# R302K.net
KiCad netlist of a schematic drawn in EAGLE
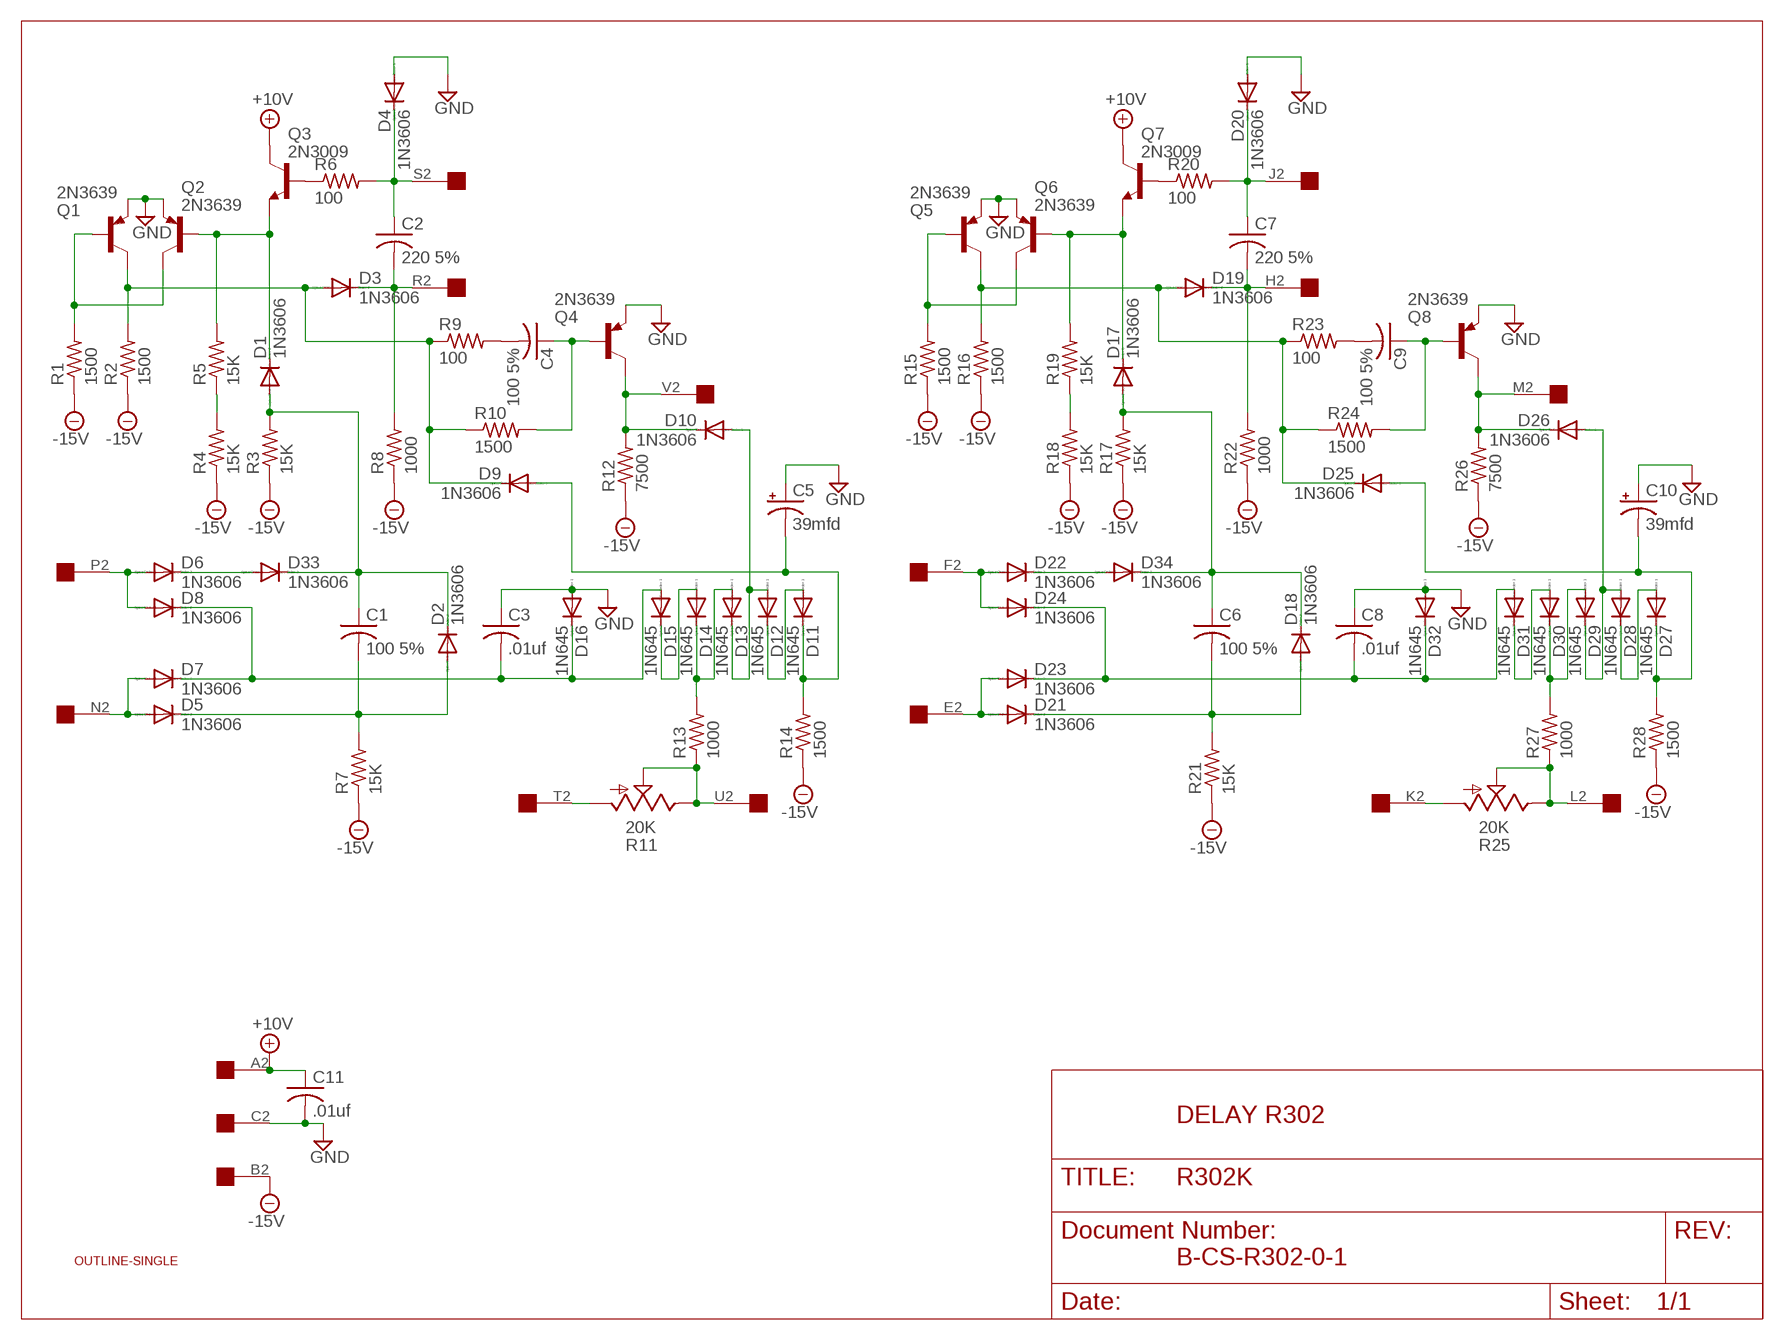
[diagram p0: schematic, sheet 1]

(export (version "E")
  (design (tool "Eeschema 10.0.6"))
  (components
    (comp (ref "C1")
      (value "100 5%")
      (footprint "eagle-import:C050-025X075")
      (libsource (lib "eagle-import") (part "C-US050-025X075"))
    )
    (comp (ref "C2")
      (value "220 5%")
      (footprint "eagle-import:C050-025X075")
      (libsource (lib "eagle-import") (part "C-US050-025X075"))
    )
    (comp (ref "C3")
      (value ".01uf")
      (footprint "eagle-import:C050-025X075")
      (libsource (lib "eagle-import") (part "C-US050-025X075"))
    )
    (comp (ref "C4")
      (value "100 5%")
      (footprint "eagle-import:C050-025X075")
      (libsource (lib "eagle-import") (part "C-US050-025X075"))
    )
    (comp (ref "C5")
      (value "39mfd")
      (footprint "eagle-import:E15-5")
      (libsource (lib "eagle-import") (part "CPOL-USE15-5AXIAL"))
    )
    (comp (ref "C6")
      (value "100 5%")
      (footprint "eagle-import:C050-025X075")
      (libsource (lib "eagle-import") (part "C-US050-025X075"))
    )
    (comp (ref "C7")
      (value "220 5%")
      (footprint "eagle-import:C050-025X075")
      (libsource (lib "eagle-import") (part "C-US050-025X075"))
    )
    (comp (ref "C8")
      (value ".01uf")
      (footprint "eagle-import:C050-025X075")
      (libsource (lib "eagle-import") (part "C-US050-025X075"))
    )
    (comp (ref "C9")
      (value "100 5%")
      (footprint "eagle-import:C050-025X075")
      (libsource (lib "eagle-import") (part "C-US050-025X075"))
    )
    (comp (ref "C10")
      (value "39mfd")
      (footprint "eagle-import:E15-5")
      (libsource (lib "eagle-import") (part "CPOL-USE15-5AXIAL"))
    )
    (comp (ref "C11")
      (value ".01uf")
      (footprint "eagle-import:C050-025X075")
      (libsource (lib "eagle-import") (part "C-US050-025X075"))
    )
    (comp (ref "D1")
      (value "1N3606")
      (footprint "eagle-import:DO35-10")
      (libsource (lib "eagle-import") (part "1N4148DO35-10"))
    )
    (comp (ref "D2")
      (value "1N3606")
      (footprint "eagle-import:DO35-10")
      (libsource (lib "eagle-import") (part "1N4148DO35-10"))
    )
    (comp (ref "D3")
      (value "1N3606")
      (footprint "eagle-import:DO35-10")
      (libsource (lib "eagle-import") (part "1N4148DO35-10"))
    )
    (comp (ref "D4")
      (value "1N3606")
      (footprint "eagle-import:DO35-10")
      (libsource (lib "eagle-import") (part "1N4148DO35-10"))
    )
    (comp (ref "D5")
      (value "1N3606")
      (footprint "eagle-import:DO35-10")
      (libsource (lib "eagle-import") (part "1N4148DO35-10"))
    )
    (comp (ref "D6")
      (value "1N3606")
      (footprint "eagle-import:DO35-10")
      (libsource (lib "eagle-import") (part "1N4148DO35-10"))
    )
    (comp (ref "D7")
      (value "1N3606")
      (footprint "eagle-import:DO35-10")
      (libsource (lib "eagle-import") (part "1N4148DO35-10"))
    )
    (comp (ref "D8")
      (value "1N3606")
      (footprint "eagle-import:DO35-10")
      (libsource (lib "eagle-import") (part "1N4148DO35-10"))
    )
    (comp (ref "D9")
      (value "1N3606")
      (footprint "eagle-import:DO35-10")
      (libsource (lib "eagle-import") (part "1N4148DO35-10"))
    )
    (comp (ref "D10")
      (value "1N3606")
      (footprint "eagle-import:DO35-10")
      (libsource (lib "eagle-import") (part "1N4148DO35-10"))
    )
    (comp (ref "D11")
      (value "1N645")
      (footprint "eagle-import:DO35-10")
      (libsource (lib "eagle-import") (part "1N4148DO35-10"))
    )
    (comp (ref "D12")
      (value "1N645")
      (footprint "eagle-import:DO35-10")
      (libsource (lib "eagle-import") (part "1N4148DO35-10"))
    )
    (comp (ref "D13")
      (value "1N645")
      (footprint "eagle-import:DO35-10")
      (libsource (lib "eagle-import") (part "1N4148DO35-10"))
    )
    (comp (ref "D14")
      (value "1N645")
      (footprint "eagle-import:DO35-10")
      (libsource (lib "eagle-import") (part "1N4148DO35-10"))
    )
    (comp (ref "D15")
      (value "1N645")
      (footprint "eagle-import:DO35-10")
      (libsource (lib "eagle-import") (part "1N4148DO35-10"))
    )
    (comp (ref "D16")
      (value "1N645")
      (footprint "eagle-import:DO35-10")
      (libsource (lib "eagle-import") (part "1N4148DO35-10"))
    )
    (comp (ref "D17")
      (value "1N3606")
      (footprint "eagle-import:DO35-10")
      (libsource (lib "eagle-import") (part "1N4148DO35-10"))
    )
    (comp (ref "D18")
      (value "1N3606")
      (footprint "eagle-import:DO35-10")
      (libsource (lib "eagle-import") (part "1N4148DO35-10"))
    )
    (comp (ref "D19")
      (value "1N3606")
      (footprint "eagle-import:DO35-10")
      (libsource (lib "eagle-import") (part "1N4148DO35-10"))
    )
    (comp (ref "D20")
      (value "1N3606")
      (footprint "eagle-import:DO35-10")
      (libsource (lib "eagle-import") (part "1N4148DO35-10"))
    )
    (comp (ref "D21")
      (value "1N3606")
      (footprint "eagle-import:DO35-10")
      (libsource (lib "eagle-import") (part "1N4148DO35-10"))
    )
    (comp (ref "D22")
      (value "1N3606")
      (footprint "eagle-import:DO35-10")
      (libsource (lib "eagle-import") (part "1N4148DO35-10"))
    )
    (comp (ref "D23")
      (value "1N3606")
      (footprint "eagle-import:DO35-10")
      (libsource (lib "eagle-import") (part "1N4148DO35-10"))
    )
    (comp (ref "D24")
      (value "1N3606")
      (footprint "eagle-import:DO35-10")
      (libsource (lib "eagle-import") (part "1N4148DO35-10"))
    )
    (comp (ref "D25")
      (value "1N3606")
      (footprint "eagle-import:DO35-10")
      (libsource (lib "eagle-import") (part "1N4148DO35-10"))
    )
    (comp (ref "D26")
      (value "1N3606")
      (footprint "eagle-import:DO35-10")
      (libsource (lib "eagle-import") (part "1N4148DO35-10"))
    )
    (comp (ref "D27")
      (value "1N645")
      (footprint "eagle-import:DO35-10")
      (libsource (lib "eagle-import") (part "1N4148DO35-10"))
    )
    (comp (ref "D28")
      (value "1N645")
      (footprint "eagle-import:DO35-10")
      (libsource (lib "eagle-import") (part "1N4148DO35-10"))
    )
    (comp (ref "D29")
      (value "1N645")
      (footprint "eagle-import:DO35-10")
      (libsource (lib "eagle-import") (part "1N4148DO35-10"))
    )
    (comp (ref "D30")
      (value "1N645")
      (footprint "eagle-import:DO35-10")
      (libsource (lib "eagle-import") (part "1N4148DO35-10"))
    )
    (comp (ref "D31")
      (value "1N645")
      (footprint "eagle-import:DO35-10")
      (libsource (lib "eagle-import") (part "1N4148DO35-10"))
    )
    (comp (ref "D32")
      (value "1N645")
      (footprint "eagle-import:DO35-10")
      (libsource (lib "eagle-import") (part "1N4148DO35-10"))
    )
    (comp (ref "D33")
      (value "1N3606")
      (footprint "eagle-import:DO35-10")
      (libsource (lib "eagle-import") (part "1N4148DO35-10"))
    )
    (comp (ref "D34")
      (value "1N3606")
      (footprint "eagle-import:DO35-10")
      (libsource (lib "eagle-import") (part "1N4148DO35-10"))
    )
    (comp (ref "Q1")
      (value "2N3639")
      (footprint "eagle-import:TO39")
      (libsource (lib "eagle-import") (part "2N3637"))
    )
    (comp (ref "Q2")
      (value "2N3639")
      (footprint "eagle-import:TO39")
      (libsource (lib "eagle-import") (part "2N3637"))
    )
    (comp (ref "Q3")
      (value "2N3009")
      (footprint "eagle-import:TO39")
      (libsource (lib "eagle-import") (part "-NPN-TO39-EBC2N3019"))
    )
    (comp (ref "Q4")
      (value "2N3639")
      (footprint "eagle-import:TO39")
      (libsource (lib "eagle-import") (part "2N3637"))
    )
    (comp (ref "Q5")
      (value "2N3639")
      (footprint "eagle-import:TO39")
      (libsource (lib "eagle-import") (part "2N3637"))
    )
    (comp (ref "Q6")
      (value "2N3639")
      (footprint "eagle-import:TO39")
      (libsource (lib "eagle-import") (part "2N3637"))
    )
    (comp (ref "Q7")
      (value "2N3009")
      (footprint "eagle-import:TO39")
      (libsource (lib "eagle-import") (part "-NPN-TO39-EBC2N3019"))
    )
    (comp (ref "Q8")
      (value "2N3639")
      (footprint "eagle-import:TO39")
      (libsource (lib "eagle-import") (part "2N3637"))
    )
    (comp (ref "R1")
      (value "1500")
      (footprint "eagle-import:0207_10")
      (libsource (lib "eagle-import") (part "R-US_0207/10"))
    )
    (comp (ref "R2")
      (value "1500")
      (footprint "eagle-import:0207_10")
      (libsource (lib "eagle-import") (part "R-US_0207/10"))
    )
    (comp (ref "R3")
      (value "15K")
      (footprint "eagle-import:0207_10")
      (libsource (lib "eagle-import") (part "R-US_0207/10"))
    )
    (comp (ref "R4")
      (value "15K")
      (footprint "eagle-import:0207_10")
      (libsource (lib "eagle-import") (part "R-US_0207/10"))
    )
    (comp (ref "R5")
      (value "15K")
      (footprint "eagle-import:0207_10")
      (libsource (lib "eagle-import") (part "R-US_0207/10"))
    )
    (comp (ref "R6")
      (value "100")
      (footprint "eagle-import:0207_10")
      (libsource (lib "eagle-import") (part "R-US_0207/10"))
    )
    (comp (ref "R7")
      (value "15K")
      (footprint "eagle-import:0207_10")
      (libsource (lib "eagle-import") (part "R-US_0207/10"))
    )
    (comp (ref "R8")
      (value "1000")
      (footprint "eagle-import:0207_10")
      (libsource (lib "eagle-import") (part "R-US_0207/10"))
    )
    (comp (ref "R9")
      (value "100")
      (footprint "eagle-import:0207_10")
      (libsource (lib "eagle-import") (part "R-US_0207/10"))
    )
    (comp (ref "R10")
      (value "1500")
      (footprint "eagle-import:0207_10")
      (libsource (lib "eagle-import") (part "R-US_0207/10"))
    )
    (comp (ref "R11")
      (value "20K")
      (footprint "eagle-import:SP19L")
      (libsource (lib "eagle-import") (part "TRIM_US-S43P"))
    )
    (comp (ref "R12")
      (value "7500")
      (footprint "eagle-import:0207_10")
      (libsource (lib "eagle-import") (part "R-US_0207/10"))
    )
    (comp (ref "R13")
      (value "1000")
      (footprint "eagle-import:0207_10")
      (libsource (lib "eagle-import") (part "R-US_0207/10"))
    )
    (comp (ref "R14")
      (value "1500")
      (footprint "eagle-import:0207_10")
      (libsource (lib "eagle-import") (part "R-US_0207/10"))
    )
    (comp (ref "R15")
      (value "1500")
      (footprint "eagle-import:0207_10")
      (libsource (lib "eagle-import") (part "R-US_0207/10"))
    )
    (comp (ref "R16")
      (value "1500")
      (footprint "eagle-import:0207_10")
      (libsource (lib "eagle-import") (part "R-US_0207/10"))
    )
    (comp (ref "R17")
      (value "15K")
      (footprint "eagle-import:0207_10")
      (libsource (lib "eagle-import") (part "R-US_0207/10"))
    )
    (comp (ref "R18")
      (value "15K")
      (footprint "eagle-import:0207_10")
      (libsource (lib "eagle-import") (part "R-US_0207/10"))
    )
    (comp (ref "R19")
      (value "15K")
      (footprint "eagle-import:0207_10")
      (libsource (lib "eagle-import") (part "R-US_0207/10"))
    )
    (comp (ref "R20")
      (value "100")
      (footprint "eagle-import:0207_10")
      (libsource (lib "eagle-import") (part "R-US_0207/10"))
    )
    (comp (ref "R21")
      (value "15K")
      (footprint "eagle-import:0207_10")
      (libsource (lib "eagle-import") (part "R-US_0207/10"))
    )
    (comp (ref "R22")
      (value "1000")
      (footprint "eagle-import:0207_10")
      (libsource (lib "eagle-import") (part "R-US_0207/10"))
    )
    (comp (ref "R23")
      (value "100")
      (footprint "eagle-import:0207_10")
      (libsource (lib "eagle-import") (part "R-US_0207/10"))
    )
    (comp (ref "R24")
      (value "1500")
      (footprint "eagle-import:0207_10")
      (libsource (lib "eagle-import") (part "R-US_0207/10"))
    )
    (comp (ref "R25")
      (value "20K")
      (footprint "eagle-import:SP19L")
      (libsource (lib "eagle-import") (part "TRIM_US-S43P"))
    )
    (comp (ref "R26")
      (value "7500")
      (footprint "eagle-import:0207_10")
      (libsource (lib "eagle-import") (part "R-US_0207/10"))
    )
    (comp (ref "R27")
      (value "1000")
      (footprint "eagle-import:0207_10")
      (libsource (lib "eagle-import") (part "R-US_0207/10"))
    )
    (comp (ref "R28")
      (value "1500")
      (footprint "eagle-import:0207_10")
      (libsource (lib "eagle-import") (part "R-US_0207/10"))
    )
    (comp (ref "U$1")
      (value "OUTLINE-SINGLE")
      (footprint "eagle-import:SINGLE")
      (libsource (lib "eagle-import") (part "OUTLINE-SINGLE"))
    )
    (comp (ref "U$2")
      (value "EDGE-1")
      (footprint "eagle-import:EDGE-CON1")
      (libsource (lib "eagle-import") (part "EDGE-1"))
    )
  )
  (nets
    (net (code "1") (name "+10V") (class "Default")
      (node (ref "C11") (pin "1") (pinfunction "1_1") (pintype "passive"))
      (node (ref "Q3") (pin "3") (pinfunction "C_3") (pintype "passive"))
      (node (ref "Q7") (pin "3") (pinfunction "C_3") (pintype "passive"))
      (node (ref "U$2") (pin "A2") (pinfunction "1_A2") (pintype "bidirectional"))
    )
    (net (code "2") (name "-15V") (class "Default")
      (node (ref "R1") (pin "1") (pinfunction "1_1") (pintype "passive"))
      (node (ref "R12") (pin "1") (pinfunction "1_1") (pintype "passive"))
      (node (ref "R14") (pin "1") (pinfunction "1_1") (pintype "passive"))
      (node (ref "R15") (pin "1") (pinfunction "1_1") (pintype "passive"))
      (node (ref "R16") (pin "1") (pinfunction "1_1") (pintype "passive"))
      (node (ref "R17") (pin "1") (pinfunction "1_1") (pintype "passive"))
      (node (ref "R18") (pin "1") (pinfunction "1_1") (pintype "passive"))
      (node (ref "R2") (pin "1") (pinfunction "1_1") (pintype "passive"))
      (node (ref "R21") (pin "1") (pinfunction "1_1") (pintype "passive"))
      (node (ref "R22") (pin "1") (pinfunction "1_1") (pintype "passive"))
      (node (ref "R26") (pin "1") (pinfunction "1_1") (pintype "passive"))
      (node (ref "R28") (pin "1") (pinfunction "1_1") (pintype "passive"))
      (node (ref "R3") (pin "1") (pinfunction "1_1") (pintype "passive"))
      (node (ref "R4") (pin "1") (pinfunction "1_1") (pintype "passive"))
      (node (ref "R7") (pin "1") (pinfunction "1_1") (pintype "passive"))
      (node (ref "R8") (pin "1") (pinfunction "1_1") (pintype "passive"))
      (node (ref "U$2") (pin "B2") (pinfunction "1_B2") (pintype "bidirectional"))
    )
    (net (code "3") (name "GND") (class "Default")
      (node (ref "C10") (pin "+") (pinfunction "+_+") (pintype "passive"))
      (node (ref "C11") (pin "2") (pinfunction "2_2") (pintype "passive"))
      (node (ref "C3") (pin "1") (pinfunction "1_1") (pintype "passive"))
      (node (ref "C5") (pin "+") (pinfunction "+_+") (pintype "passive"))
      (node (ref "C8") (pin "1") (pinfunction "1_1") (pintype "passive"))
      (node (ref "D16") (pin "A") (pinfunction "A_A") (pintype "passive"))
      (node (ref "D20") (pin "A") (pinfunction "A_A") (pintype "passive"))
      (node (ref "D32") (pin "A") (pinfunction "A_A") (pintype "passive"))
      (node (ref "D4") (pin "A") (pinfunction "A_A") (pintype "passive"))
      (node (ref "Q1") (pin "1") (pinfunction "E_1") (pintype "passive"))
      (node (ref "Q2") (pin "1") (pinfunction "E_1") (pintype "passive"))
      (node (ref "Q4") (pin "1") (pinfunction "E_1") (pintype "passive"))
      (node (ref "Q5") (pin "1") (pinfunction "E_1") (pintype "passive"))
      (node (ref "Q6") (pin "1") (pinfunction "E_1") (pintype "passive"))
      (node (ref "Q8") (pin "1") (pinfunction "E_1") (pintype "passive"))
      (node (ref "U$2") (pin "C2") (pinfunction "1_C2") (pintype "bidirectional"))
    )
    (net (code "4") (name "Net-(C1-Pad1)") (class "Default")
      (node (ref "C1") (pin "1") (pinfunction "1_1") (pintype "passive"))
      (node (ref "D1") (pin "A") (pinfunction "A_A") (pintype "passive"))
      (node (ref "D2") (pin "C") (pinfunction "C_C") (pintype "passive"))
      (node (ref "D33") (pin "C") (pinfunction "C_C") (pintype "passive"))
      (node (ref "R3") (pin "2") (pinfunction "2_2") (pintype "passive"))
    )
    (net (code "5") (name "Net-(C1-Pad2)") (class "Default")
      (node (ref "C1") (pin "2") (pinfunction "2_2") (pintype "passive"))
      (node (ref "D2") (pin "A") (pinfunction "A_A") (pintype "passive"))
      (node (ref "D5") (pin "C") (pinfunction "C_C") (pintype "passive"))
      (node (ref "R7") (pin "2") (pinfunction "2_2") (pintype "passive"))
    )
    (net (code "6") (name "Net-(C3-Pad2)") (class "Default")
      (node (ref "C3") (pin "2") (pinfunction "2_2") (pintype "passive"))
      (node (ref "D15") (pin "A") (pinfunction "A_A") (pintype "passive"))
      (node (ref "D16") (pin "C") (pinfunction "C_C") (pintype "passive"))
      (node (ref "D7") (pin "C") (pinfunction "C_C") (pintype "passive"))
      (node (ref "D8") (pin "C") (pinfunction "C_C") (pintype "passive"))
    )
    (net (code "7") (name "Net-(C4-Pad2)") (class "Default")
      (node (ref "C4") (pin "2") (pinfunction "2_2") (pintype "passive"))
      (node (ref "R9") (pin "2") (pinfunction "2_2") (pintype "passive"))
    )
    (net (code "8") (name "Net-(C5-Pad-)") (class "Default")
      (node (ref "C5") (pin "-") (pinfunction "-_-") (pintype "passive"))
      (node (ref "D11") (pin "C") (pinfunction "C_C") (pintype "passive"))
      (node (ref "D9") (pin "A") (pinfunction "A_A") (pintype "passive"))
      (node (ref "R14") (pin "2") (pinfunction "2_2") (pintype "passive"))
    )
    (net (code "9") (name "Net-(C6-Pad1)") (class "Default")
      (node (ref "C6") (pin "1") (pinfunction "1_1") (pintype "passive"))
      (node (ref "D17") (pin "A") (pinfunction "A_A") (pintype "passive"))
      (node (ref "D18") (pin "C") (pinfunction "C_C") (pintype "passive"))
      (node (ref "D34") (pin "C") (pinfunction "C_C") (pintype "passive"))
      (node (ref "R17") (pin "2") (pinfunction "2_2") (pintype "passive"))
    )
    (net (code "10") (name "Net-(C6-Pad2)") (class "Default")
      (node (ref "C6") (pin "2") (pinfunction "2_2") (pintype "passive"))
      (node (ref "D18") (pin "A") (pinfunction "A_A") (pintype "passive"))
      (node (ref "D21") (pin "C") (pinfunction "C_C") (pintype "passive"))
      (node (ref "R21") (pin "2") (pinfunction "2_2") (pintype "passive"))
    )
    (net (code "11") (name "Net-(C8-Pad2)") (class "Default")
      (node (ref "C8") (pin "2") (pinfunction "2_2") (pintype "passive"))
      (node (ref "D23") (pin "C") (pinfunction "C_C") (pintype "passive"))
      (node (ref "D24") (pin "C") (pinfunction "C_C") (pintype "passive"))
      (node (ref "D31") (pin "A") (pinfunction "A_A") (pintype "passive"))
      (node (ref "D32") (pin "C") (pinfunction "C_C") (pintype "passive"))
    )
    (net (code "12") (name "Net-(C9-Pad2)") (class "Default")
      (node (ref "C9") (pin "2") (pinfunction "2_2") (pintype "passive"))
      (node (ref "R23") (pin "2") (pinfunction "2_2") (pintype "passive"))
    )
    (net (code "13") (name "Net-(C10-Pad-)") (class "Default")
      (node (ref "C10") (pin "-") (pinfunction "-_-") (pintype "passive"))
      (node (ref "D25") (pin "A") (pinfunction "A_A") (pintype "passive"))
      (node (ref "D27") (pin "C") (pinfunction "C_C") (pintype "passive"))
      (node (ref "R28") (pin "2") (pinfunction "2_2") (pintype "passive"))
    )
    (net (code "14") (name "Net-(D10-PadA)") (class "Default")
      (node (ref "D10") (pin "A") (pinfunction "A_A") (pintype "passive"))
      (node (ref "D12") (pin "A") (pinfunction "A_A") (pintype "passive"))
      (node (ref "D13") (pin "C") (pinfunction "C_C") (pintype "passive"))
    )
    (net (code "15") (name "Net-(D11-PadA)") (class "Default")
      (node (ref "D11") (pin "A") (pinfunction "A_A") (pintype "passive"))
      (node (ref "D12") (pin "C") (pinfunction "C_C") (pintype "passive"))
    )
    (net (code "16") (name "Net-(D13-PadA)") (class "Default")
      (node (ref "D13") (pin "A") (pinfunction "A_A") (pintype "passive"))
      (node (ref "D14") (pin "C") (pinfunction "C_C") (pintype "passive"))
      (node (ref "R13") (pin "2") (pinfunction "2_2") (pintype "passive"))
    )
    (net (code "17") (name "Net-(D14-PadA)") (class "Default")
      (node (ref "D14") (pin "A") (pinfunction "A_A") (pintype "passive"))
      (node (ref "D15") (pin "C") (pinfunction "C_C") (pintype "passive"))
    )
    (net (code "18") (name "Net-(D22-PadC)") (class "Default")
      (node (ref "D22") (pin "C") (pinfunction "C_C") (pintype "passive"))
      (node (ref "D34") (pin "A") (pinfunction "A_A") (pintype "passive"))
    )
    (net (code "19") (name "Net-(D26-PadA)") (class "Default")
      (node (ref "D26") (pin "A") (pinfunction "A_A") (pintype "passive"))
      (node (ref "D28") (pin "A") (pinfunction "A_A") (pintype "passive"))
      (node (ref "D29") (pin "C") (pinfunction "C_C") (pintype "passive"))
    )
    (net (code "20") (name "Net-(D27-PadA)") (class "Default")
      (node (ref "D27") (pin "A") (pinfunction "A_A") (pintype "passive"))
      (node (ref "D28") (pin "C") (pinfunction "C_C") (pintype "passive"))
    )
    (net (code "21") (name "Net-(D29-PadA)") (class "Default")
      (node (ref "D29") (pin "A") (pinfunction "A_A") (pintype "passive"))
      (node (ref "D30") (pin "C") (pinfunction "C_C") (pintype "passive"))
      (node (ref "R27") (pin "2") (pinfunction "2_2") (pintype "passive"))
    )
    (net (code "22") (name "Net-(D30-PadA)") (class "Default")
      (node (ref "D30") (pin "A") (pinfunction "A_A") (pintype "passive"))
      (node (ref "D31") (pin "C") (pinfunction "C_C") (pintype "passive"))
    )
    (net (code "23") (name "Net-(D33-PadA)") (class "Default")
      (node (ref "D33") (pin "A") (pinfunction "A_A") (pintype "passive"))
      (node (ref "D6") (pin "C") (pinfunction "C_C") (pintype "passive"))
    )
    (net (code "24") (name "Net-(Q1-B)") (class "Default")
      (node (ref "Q1") (pin "2") (pinfunction "B_2") (pintype "passive"))
      (node (ref "Q2") (pin "3") (pinfunction "C_3") (pintype "passive"))
      (node (ref "R1") (pin "2") (pinfunction "2_2") (pintype "passive"))
    )
    (net (code "25") (name "Net-(Q1-C)") (class "Default")
      (node (ref "D3") (pin "A") (pinfunction "A_A") (pintype "passive"))
      (node (ref "D9") (pin "C") (pinfunction "C_C") (pintype "passive"))
      (node (ref "Q1") (pin "3") (pinfunction "C_3") (pintype "passive"))
      (node (ref "R10") (pin "1") (pinfunction "1_1") (pintype "passive"))
      (node (ref "R2") (pin "2") (pinfunction "2_2") (pintype "passive"))
      (node (ref "R9") (pin "1") (pinfunction "1_1") (pintype "passive"))
    )
    (net (code "26") (name "Net-(Q2-B)") (class "Default")
      (node (ref "D1") (pin "C") (pinfunction "C_C") (pintype "passive"))
      (node (ref "Q2") (pin "2") (pinfunction "B_2") (pintype "passive"))
      (node (ref "Q3") (pin "1") (pinfunction "E_1") (pintype "passive"))
      (node (ref "R5") (pin "2") (pinfunction "2_2") (pintype "passive"))
    )
    (net (code "27") (name "Net-(Q3-B)") (class "Default")
      (node (ref "Q3") (pin "2") (pinfunction "B_2") (pintype "passive"))
      (node (ref "R6") (pin "1") (pinfunction "1_1") (pintype "passive"))
    )
    (net (code "28") (name "Net-(Q4-B)") (class "Default")
      (node (ref "C4") (pin "1") (pinfunction "1_1") (pintype "passive"))
      (node (ref "Q4") (pin "2") (pinfunction "B_2") (pintype "passive"))
      (node (ref "R10") (pin "2") (pinfunction "2_2") (pintype "passive"))
    )
    (net (code "29") (name "Net-(Q4-C)") (class "Default")
      (node (ref "D10") (pin "C") (pinfunction "C_C") (pintype "passive"))
      (node (ref "Q4") (pin "3") (pinfunction "C_3") (pintype "passive"))
      (node (ref "R12") (pin "2") (pinfunction "2_2") (pintype "passive"))
      (node (ref "U$2") (pin "V2") (pinfunction "1_V2") (pintype "bidirectional"))
    )
    (net (code "30") (name "Net-(Q5-B)") (class "Default")
      (node (ref "Q5") (pin "2") (pinfunction "B_2") (pintype "passive"))
      (node (ref "Q6") (pin "3") (pinfunction "C_3") (pintype "passive"))
      (node (ref "R15") (pin "2") (pinfunction "2_2") (pintype "passive"))
    )
    (net (code "31") (name "Net-(Q5-C)") (class "Default")
      (node (ref "D19") (pin "A") (pinfunction "A_A") (pintype "passive"))
      (node (ref "D25") (pin "C") (pinfunction "C_C") (pintype "passive"))
      (node (ref "Q5") (pin "3") (pinfunction "C_3") (pintype "passive"))
      (node (ref "R16") (pin "2") (pinfunction "2_2") (pintype "passive"))
      (node (ref "R23") (pin "1") (pinfunction "1_1") (pintype "passive"))
      (node (ref "R24") (pin "1") (pinfunction "1_1") (pintype "passive"))
    )
    (net (code "32") (name "Net-(Q6-B)") (class "Default")
      (node (ref "D17") (pin "C") (pinfunction "C_C") (pintype "passive"))
      (node (ref "Q6") (pin "2") (pinfunction "B_2") (pintype "passive"))
      (node (ref "Q7") (pin "1") (pinfunction "E_1") (pintype "passive"))
      (node (ref "R19") (pin "2") (pinfunction "2_2") (pintype "passive"))
    )
    (net (code "33") (name "Net-(Q7-B)") (class "Default")
      (node (ref "Q7") (pin "2") (pinfunction "B_2") (pintype "passive"))
      (node (ref "R20") (pin "1") (pinfunction "1_1") (pintype "passive"))
    )
    (net (code "34") (name "Net-(Q8-B)") (class "Default")
      (node (ref "C9") (pin "1") (pinfunction "1_1") (pintype "passive"))
      (node (ref "Q8") (pin "2") (pinfunction "B_2") (pintype "passive"))
      (node (ref "R24") (pin "2") (pinfunction "2_2") (pintype "passive"))
    )
    (net (code "35") (name "Net-(Q8-C)") (class "Default")
      (node (ref "D26") (pin "C") (pinfunction "C_C") (pintype "passive"))
      (node (ref "Q8") (pin "3") (pinfunction "C_3") (pintype "passive"))
      (node (ref "R26") (pin "2") (pinfunction "2_2") (pintype "passive"))
      (node (ref "U$2") (pin "M2") (pinfunction "1_M2") (pintype "bidirectional"))
    )
    (net (code "36") (name "Net-(R4-Pad2)") (class "Default")
      (node (ref "R4") (pin "2") (pinfunction "2_2") (pintype "passive"))
      (node (ref "R5") (pin "1") (pinfunction "1_1") (pintype "passive"))
    )
    (net (code "37") (name "Net-(R18-Pad2)") (class "Default")
      (node (ref "R18") (pin "2") (pinfunction "2_2") (pintype "passive"))
      (node (ref "R19") (pin "1") (pinfunction "1_1") (pintype "passive"))
    )
    (net (code "38") (name "Net-(U$2E-1)") (class "Default")
      (node (ref "D21") (pin "A") (pinfunction "A_A") (pintype "passive"))
      (node (ref "D23") (pin "A") (pinfunction "A_A") (pintype "passive"))
      (node (ref "U$2") (pin "E2") (pinfunction "1_E2") (pintype "bidirectional"))
    )
    (net (code "39") (name "Net-(U$2F-1)") (class "Default")
      (node (ref "D22") (pin "A") (pinfunction "A_A") (pintype "passive"))
      (node (ref "D24") (pin "A") (pinfunction "A_A") (pintype "passive"))
      (node (ref "U$2") (pin "F2") (pinfunction "1_F2") (pintype "bidirectional"))
    )
    (net (code "40") (name "Net-(U$2G-1)") (class "Default")
      (node (ref "C7") (pin "2") (pinfunction "2_2") (pintype "passive"))
      (node (ref "D19") (pin "C") (pinfunction "C_C") (pintype "passive"))
      (node (ref "R22") (pin "2") (pinfunction "2_2") (pintype "passive"))
      (node (ref "U$2") (pin "H2") (pinfunction "1_H2") (pintype "bidirectional"))
    )
    (net (code "41") (name "Net-(U$2H-1)") (class "Default")
      (node (ref "C7") (pin "1") (pinfunction "1_1") (pintype "passive"))
      (node (ref "D20") (pin "C") (pinfunction "C_C") (pintype "passive"))
      (node (ref "R20") (pin "2") (pinfunction "2_2") (pintype "passive"))
      (node (ref "U$2") (pin "J2") (pinfunction "1_J2") (pintype "bidirectional"))
    )
    (net (code "42") (name "Net-(U$2I-1)") (class "Default")
      (node (ref "R25") (pin "A") (pinfunction "A_A") (pintype "passive"))
      (node (ref "U$2") (pin "K2") (pinfunction "1_K2") (pintype "bidirectional"))
    )
    (net (code "43") (name "Net-(U$2J-1)") (class "Default")
      (node (ref "R25") (pin "E") (pinfunction "E_E") (pintype "passive"))
      (node (ref "R25") (pin "S") (pinfunction "S_S") (pintype "passive"))
      (node (ref "R27") (pin "1") (pinfunction "1_1") (pintype "passive"))
      (node (ref "U$2") (pin "L2") (pinfunction "1_L2") (pintype "bidirectional"))
    )
    (net (code "44") (name "Net-(U$2L-1)") (class "Default")
      (node (ref "D5") (pin "A") (pinfunction "A_A") (pintype "passive"))
      (node (ref "D7") (pin "A") (pinfunction "A_A") (pintype "passive"))
      (node (ref "U$2") (pin "N2") (pinfunction "1_N2") (pintype "bidirectional"))
    )
    (net (code "45") (name "Net-(U$2M-1)") (class "Default")
      (node (ref "D6") (pin "A") (pinfunction "A_A") (pintype "passive"))
      (node (ref "D8") (pin "A") (pinfunction "A_A") (pintype "passive"))
      (node (ref "U$2") (pin "P2") (pinfunction "1_P2") (pintype "bidirectional"))
    )
    (net (code "46") (name "Net-(U$2N-1)") (class "Default")
      (node (ref "C2") (pin "2") (pinfunction "2_2") (pintype "passive"))
      (node (ref "D3") (pin "C") (pinfunction "C_C") (pintype "passive"))
      (node (ref "R8") (pin "2") (pinfunction "2_2") (pintype "passive"))
      (node (ref "U$2") (pin "R2") (pinfunction "1_R2") (pintype "bidirectional"))
    )
    (net (code "47") (name "Net-(U$2O-1)") (class "Default")
      (node (ref "C2") (pin "1") (pinfunction "1_1") (pintype "passive"))
      (node (ref "D4") (pin "C") (pinfunction "C_C") (pintype "passive"))
      (node (ref "R6") (pin "2") (pinfunction "2_2") (pintype "passive"))
      (node (ref "U$2") (pin "S2") (pinfunction "1_S2") (pintype "bidirectional"))
    )
    (net (code "48") (name "Net-(U$2P-1)") (class "Default")
      (node (ref "R11") (pin "A") (pinfunction "A_A") (pintype "passive"))
      (node (ref "U$2") (pin "T2") (pinfunction "1_T2") (pintype "bidirectional"))
    )
    (net (code "49") (name "Net-(U$2Q-1)") (class "Default")
      (node (ref "R11") (pin "E") (pinfunction "E_E") (pintype "passive"))
      (node (ref "R11") (pin "S") (pinfunction "S_S") (pintype "passive"))
      (node (ref "R13") (pin "1") (pinfunction "1_1") (pintype "passive"))
      (node (ref "U$2") (pin "U2") (pinfunction "1_U2") (pintype "bidirectional"))
    )
  )
)
